# Temperature.net
KiCad netlist of a schematic drawn in Altium Designer
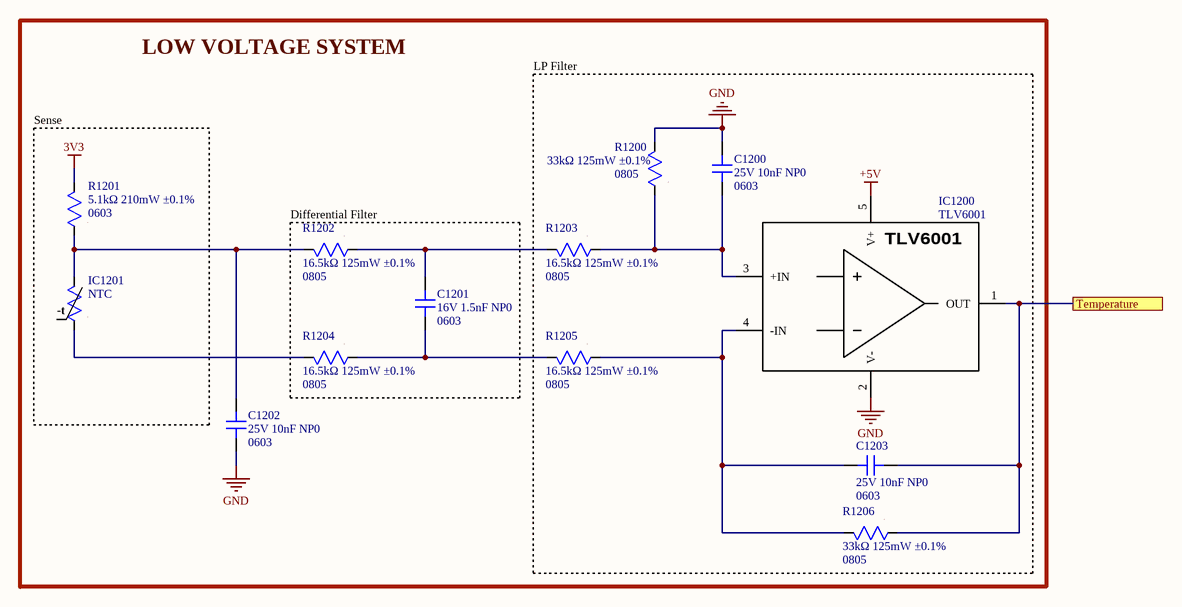
[diagram p0: Temperature.SchDoc]

(export (version "E")
  (design (tool "Eeschema 10.0.6"))
  (components
    (comp (ref "C1200")
      (value "25V 10nF NP0")
      (footprint "CAP SMD 0603")
      (description "Condensadores de cerámica multicapa (MLCC- SMD/SMT) 0.01 uF 25 VDC 1% 0603 C0G (NP0) AEC-Q200")
      (fields
        (field (name "PACKAGE") "0603")
        (field (name "MPN") "GRT1885C1E103FA02D")
        (field (name "MANUFACTURER") "muRata")
      )
      (libsource (lib "eUSR_Database") (part "CAP non polarized"))
    )
    (comp (ref "C1201")
      (value "16V 1.5nF NP0")
      (footprint "CAP SMD 0603")
      (description "Condensadores de cerámica multicapa (MLCC- SMD/SMT) 25V 1500pF C0G 0603 1%")
      (fields
        (field (name "PACKAGE") "0603")
        (field (name "MPN") "C0603C152F3GECTU")
        (field (name "MANUFACTURER") "KEMET")
      )
      (libsource (lib "eUSR_Database") (part "CAP non polarized"))
    )
    (comp (ref "C1202")
      (value "25V 10nF NP0")
      (footprint "CAP SMD 0603")
      (description "Condensadores de cerámica multicapa (MLCC- SMD/SMT) 50V 5100pF 0603 C0G 1%")
      (fields
        (field (name "PACKAGE") "0603")
        (field (name "MPN") "C0603C512F5GACTU")
        (field (name "MANUFACTURER") "KEMET")
      )
      (libsource (lib "eUSR_Database") (part "CAP non polarized"))
    )
    (comp (ref "C1203")
      (value "25V 10nF NP0")
      (footprint "CAP SMD 0603")
      (description "Condensadores de cerámica multicapa (MLCC- SMD/SMT) 0.01 uF 25 VDC 1% 0603 C0G (NP0) AEC-Q200")
      (fields
        (field (name "PACKAGE") "0603")
        (field (name "MPN") "GRT1885C1E103FA02D")
        (field (name "MANUFACTURER") "muRata")
      )
      (libsource (lib "eUSR_Database") (part "CAP non polarized"))
    )
    (comp (ref "IC1200")
      (value "TLV6001")
      (footprint "SOT-23-5")
      (fields (field (name "MPN") "TLV6001UIDBVR") (field (name "MANUFACTURER") "Texas Instruments"))
      (libsource (lib "eUSR_Database") (part "TLV6001"))
    )
    (comp (ref "IC1201")
      (value "NTC")
      (footprint "RES SMD 0603")
      (description "Termistores NTC 10Kohms 1% SMD")
      (fields (field (name "MPN") "NTCS0603E3103FLT") (field (name "MANUFACTURER") "Vishay"))
      (libsource (lib "eUSR_Database") (part "NTC"))
    )
    (comp (ref "R1200")
      (value "33kΩ 125mW ±0.1%")
      (footprint "RES SMD 0805")
      (description "Thin Film Resistors 0805 33Kohm 0.1% 15ppm AEC-Q200")
      (fields
        (field (name "PACKAGE") "0805")
        (field (name "MPN") "ERA-6APB333V")
        (field (name "MANUFACTURER") "Panasonic")
      )
      (libsource (lib "eUSR_Database") (part "RES"))
    )
    (comp (ref "R1201")
      (value "5.1kΩ 210mW ±0.1%")
      (footprint "RES SMD 0603")
      (description "Thin Film Resistors 5.1Kohms 0.1% 10ppm")
      (fields
        (field (name "PACKAGE") "0603")
        (field (name "MPN") "TNPW06035K10BYEN")
        (field (name "MANUFACTURER") "Vishay")
      )
      (libsource (lib "eUSR_Database") (part "RES"))
    )
    (comp (ref "R1202")
      (value "16.5kΩ 125mW ±0.1%")
      (footprint "RES SMD 0805")
      (description "Thin Film Resistors 0805 Thin film chip resistor")
      (fields
        (field (name "PACKAGE") "0805")
        (field (name "MPN") "ERA-6ARB1652V")
        (field (name "MANUFACTURER") "Panasonic")
      )
      (libsource (lib "eUSR_Database") (part "RES"))
    )
    (comp (ref "R1203")
      (value "16.5kΩ 125mW ±0.1%")
      (footprint "RES SMD 0805")
      (description "Thin Film Resistors 0805 Thin film chip resistor")
      (fields
        (field (name "PACKAGE") "0805")
        (field (name "MPN") "ERA-6ARB1652V")
        (field (name "MANUFACTURER") "Panasonic")
      )
      (libsource (lib "eUSR_Database") (part "RES"))
    )
    (comp (ref "R1204")
      (value "16.5kΩ 125mW ±0.1%")
      (footprint "RES SMD 0805")
      (description "Thin Film Resistors 0805 Thin film chip resistor")
      (fields
        (field (name "PACKAGE") "0805")
        (field (name "MPN") "ERA-6ARB1652V")
        (field (name "MANUFACTURER") "Panasonic")
      )
      (libsource (lib "eUSR_Database") (part "RES"))
    )
    (comp (ref "R1205")
      (value "16.5kΩ 125mW ±0.1%")
      (footprint "RES SMD 0805")
      (description "Thin Film Resistors 0805 Thin film chip resistor")
      (fields
        (field (name "PACKAGE") "0805")
        (field (name "MPN") "ERA-6ARB1652V")
        (field (name "MANUFACTURER") "Panasonic")
      )
      (libsource (lib "eUSR_Database") (part "RES"))
    )
    (comp (ref "R1206")
      (value "33kΩ 125mW ±0.1%")
      (footprint "RES SMD 0805")
      (description "Thin Film Resistors 0805 33Kohm 0.1% 15ppm AEC-Q200")
      (fields
        (field (name "PACKAGE") "0805")
        (field (name "MPN") "ERA-6APB333V")
        (field (name "MANUFACTURER") "Panasonic")
      )
      (libsource (lib "eUSR_Database") (part "RES"))
    )
  )
  (nets
    (net (code "1") (name "+5V") (class "Default")
      (node (ref "IC1200") (pin "5") (pinfunction "V+_5") (pintype "passive"))
    )
    (net (code "2") (name "/Temperature") (class "Default")
      (node (ref "C1203") (pin "2") (pinfunction "2_2") (pintype "passive"))
      (node (ref "IC1200") (pin "1") (pinfunction "OUT_1") (pintype "passive"))
      (node (ref "R1206") (pin "1") (pinfunction "1_1") (pintype "passive"))
    )
    (net (code "3") (name "3V3") (class "Default")
      (node (ref "R1201") (pin "2") (pinfunction "2_2") (pintype "passive"))
    )
    (net (code "4") (name "GND") (class "Default")
      (node (ref "C1200") (pin "2") (pinfunction "2_2") (pintype "passive"))
      (node (ref "C1202") (pin "2") (pinfunction "2_2") (pintype "passive"))
      (node (ref "IC1200") (pin "2") (pinfunction "V-_2") (pintype "passive"))
      (node (ref "R1200") (pin "2") (pinfunction "2_2") (pintype "passive"))
    )
    (net (code "5") (name "Net-(C1201-Pad1)") (class "Default")
      (node (ref "C1201") (pin "1") (pinfunction "1_1") (pintype "passive"))
      (node (ref "R1202") (pin "1") (pinfunction "1_1") (pintype "passive"))
      (node (ref "R1203") (pin "2") (pinfunction "2_2") (pintype "passive"))
    )
    (net (code "6") (name "Net-(C1201-Pad2)") (class "Default")
      (node (ref "C1201") (pin "2") (pinfunction "2_2") (pintype "passive"))
      (node (ref "R1204") (pin "1") (pinfunction "1_1") (pintype "passive"))
      (node (ref "R1205") (pin "2") (pinfunction "2_2") (pintype "passive"))
    )
    (net (code "7") (name "Net-(C1202-Pad1)") (class "Default")
      (node (ref "C1202") (pin "1") (pinfunction "1_1") (pintype "passive"))
      (node (ref "IC1201") (pin "2") (pinfunction "2_2") (pintype "passive"))
      (node (ref "R1201") (pin "1") (pinfunction "1_1") (pintype "passive"))
      (node (ref "R1202") (pin "2") (pinfunction "2_2") (pintype "passive"))
    )
    (net (code "8") (name "Net-(IC1200-+IN)") (class "Default")
      (node (ref "C1200") (pin "1") (pinfunction "1_1") (pintype "passive"))
      (node (ref "IC1200") (pin "3") (pinfunction "+IN_3") (pintype "passive"))
      (node (ref "R1200") (pin "1") (pinfunction "1_1") (pintype "passive"))
      (node (ref "R1203") (pin "1") (pinfunction "1_1") (pintype "passive"))
    )
    (net (code "9") (name "Net-(IC1200--IN)") (class "Default")
      (node (ref "C1203") (pin "1") (pinfunction "1_1") (pintype "passive"))
      (node (ref "IC1200") (pin "4") (pinfunction "-IN_4") (pintype "passive"))
      (node (ref "R1205") (pin "1") (pinfunction "1_1") (pintype "passive"))
      (node (ref "R1206") (pin "2") (pinfunction "2_2") (pintype "passive"))
    )
    (net (code "10") (name "Net-(IC1201-Pad1)") (class "Default")
      (node (ref "IC1201") (pin "1") (pinfunction "1_1") (pintype "passive"))
      (node (ref "R1204") (pin "2") (pinfunction "2_2") (pintype "passive"))
    )
  )
)
